# um66t.net
KiCad netlist of a schematic drawn in EAGLE
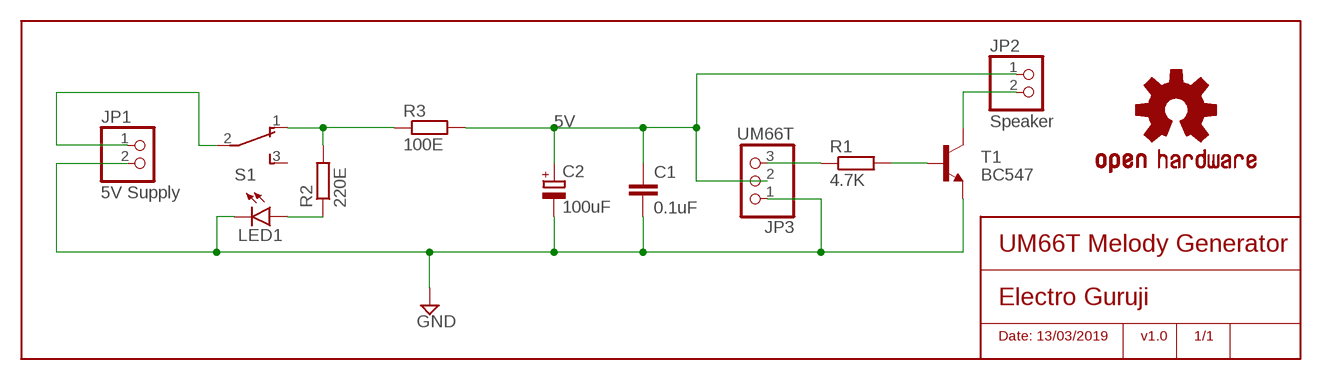
[diagram p0: schematic, sheet 1]

(export (version "E")
  (design (tool "Eeschema 10.0.6"))
  (components
    (comp (ref "C1")
      (value "0.1uF")
      (footprint "eagle-import:C025-024X044")
      (libsource (lib "eagle-import") (part "C-EU025-024X044"))
    )
    (comp (ref "C2")
      (value "100uF")
      (footprint "eagle-import:E5-5")
      (libsource (lib "eagle-import") (part "CPOL-EUE5-5"))
    )
    (comp (ref "JP1")
      (value "5V Supply")
      (footprint "eagle-import:1X02")
      (libsource (lib "eagle-import") (part "PINHD-1X2"))
    )
    (comp (ref "JP2")
      (value "Speaker")
      (footprint "eagle-import:1X02")
      (libsource (lib "eagle-import") (part "PINHD-1X2"))
    )
    (comp (ref "JP3")
      (value "UM66T")
      (footprint "eagle-import:1X03")
      (libsource (lib "eagle-import") (part "PINHD-1X3"))
    )
    (comp (ref "LED1")
      (value "LED5MM")
      (footprint "eagle-import:LED5MM")
      (libsource (lib "eagle-import") (part "LED5MM"))
    )
    (comp (ref "LOGO1")
      (value "OSHW-LOGOM-COPPER")
      (footprint "eagle-import:OSHW-LOGO-M_COPPER")
      (libsource (lib "eagle-import") (part "OSHW-LOGOM-COPPER"))
    )
    (comp (ref "R1")
      (value "4.7K")
      (footprint "eagle-import:0204_5")
      (libsource (lib "eagle-import") (part "R-EU_0204/5"))
    )
    (comp (ref "R2")
      (value "220E")
      (footprint "eagle-import:0204_5")
      (libsource (lib "eagle-import") (part "R-EU_0204/5"))
    )
    (comp (ref "R3")
      (value "100E")
      (footprint "eagle-import:0204_5")
      (libsource (lib "eagle-import") (part "R-EU_0204/5"))
    )
    (comp (ref "S1")
      (value "SPDT")
      (footprint "eagle-import:TL3XYO")
      (libsource (lib "eagle-import") (part "TL36YO"))
    )
    (comp (ref "T1")
      (value "BC547")
      (footprint "eagle-import:TO92-CBE")
      (libsource (lib "eagle-import") (part "-NPN-TO92-CBEBC237"))
    )
  )
  (nets
    (net (code "1") (name "/5V") (class "Default")
      (node (ref "C1") (pin "1") (pinfunction "1_1") (pintype "passive"))
      (node (ref "C2") (pin "+") (pinfunction "+_+") (pintype "passive"))
      (node (ref "JP2") (pin "1") (pinfunction "1_1") (pintype "passive"))
      (node (ref "JP3") (pin "2") (pinfunction "2_2") (pintype "passive"))
      (node (ref "R3") (pin "2") (pinfunction "2_2") (pintype "passive"))
    )
    (net (code "2") (name "GND") (class "Default")
      (node (ref "C1") (pin "2") (pinfunction "2_2") (pintype "passive"))
      (node (ref "C2") (pin "-") (pinfunction "-_-") (pintype "passive"))
      (node (ref "JP1") (pin "2") (pinfunction "2_2") (pintype "passive"))
      (node (ref "JP3") (pin "1") (pinfunction "1_1") (pintype "passive"))
      (node (ref "LED1") (pin "K") (pinfunction "C_K") (pintype "passive"))
      (node (ref "T1") (pin "E") (pinfunction "E_E") (pintype "passive"))
    )
    (net (code "3") (name "Net-(JP2-Pad2)") (class "Default")
      (node (ref "JP2") (pin "2") (pinfunction "2_2") (pintype "passive"))
      (node (ref "T1") (pin "C") (pinfunction "C_C") (pintype "passive"))
    )
    (net (code "4") (name "Net-(JP3-Pad3)") (class "Default")
      (node (ref "JP3") (pin "3") (pinfunction "3_3") (pintype "passive"))
      (node (ref "R1") (pin "1") (pinfunction "1_1") (pintype "passive"))
    )
    (net (code "5") (name "Net-(LED1-PadA)") (class "Default")
      (node (ref "LED1") (pin "A") (pinfunction "A_A") (pintype "passive"))
      (node (ref "R2") (pin "1") (pinfunction "1_1") (pintype "passive"))
    )
    (net (code "6") (name "Net-(R1-Pad2)") (class "Default")
      (node (ref "R1") (pin "2") (pinfunction "2_2") (pintype "passive"))
      (node (ref "T1") (pin "B") (pinfunction "B_B") (pintype "passive"))
    )
    (net (code "7") (name "Net-(S1-O)") (class "Default")
      (node (ref "R2") (pin "2") (pinfunction "2_2") (pintype "passive"))
      (node (ref "R3") (pin "1") (pinfunction "1_1") (pintype "passive"))
      (node (ref "S1") (pin "1") (pinfunction "O_1") (pintype "passive"))
    )
    (net (code "8") (name "Net-(S1-P)") (class "Default")
      (node (ref "JP1") (pin "1") (pinfunction "1_1") (pintype "passive"))
      (node (ref "S1") (pin "2") (pinfunction "P_2") (pintype "passive"))
    )
    (net (code "9") (name "unconnected-(S1-S-Pad3)") (class "Default")
      (node (ref "S1") (pin "3") (pinfunction "S_3") (pintype "passive"))
    )
  )
)
